# stepper_driver1_a.net
KiCad netlist of a schematic drawn in EAGLE
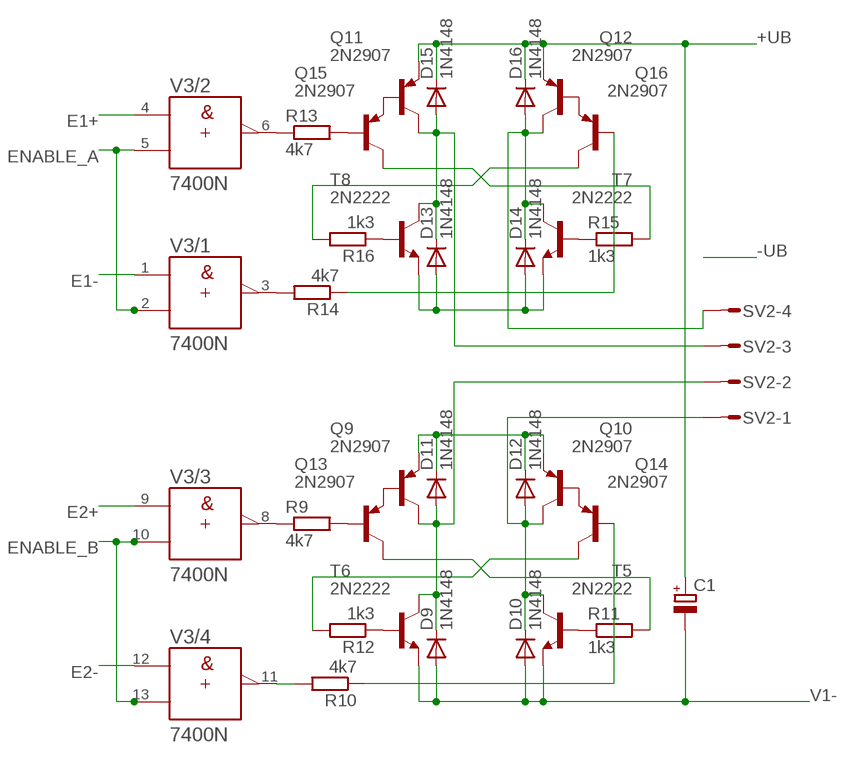
[diagram p0: schematic, sheet 1]

(export (version "E")
  (design (tool "Eeschema 10.0.6"))
  (components
    (comp (ref "C1")
      (value "CPOL-EUE3.5-10")
      (footprint "eagle-import:E3,5-10")
      (libsource (lib "eagle-import") (part "CPOL-EUE3.5-10"))
    )
    (comp (ref "D9")
      (value "1N4148")
      (footprint "eagle-import:D-2.5")
      (libsource (lib "eagle-import") (part "DIODE-D-2.5"))
    )
    (comp (ref "D10")
      (value "1N4148")
      (footprint "eagle-import:D-2.5")
      (libsource (lib "eagle-import") (part "DIODE-D-2.5"))
    )
    (comp (ref "D11")
      (value "1N4148")
      (footprint "eagle-import:D-2.5")
      (libsource (lib "eagle-import") (part "DIODE-D-2.5"))
    )
    (comp (ref "D12")
      (value "1N4148")
      (footprint "eagle-import:D-2.5")
      (libsource (lib "eagle-import") (part "DIODE-D-2.5"))
    )
    (comp (ref "D13")
      (value "1N4148")
      (footprint "eagle-import:D-2.5")
      (libsource (lib "eagle-import") (part "DIODE-D-2.5"))
    )
    (comp (ref "D14")
      (value "1N4148")
      (footprint "eagle-import:D-2.5")
      (libsource (lib "eagle-import") (part "DIODE-D-2.5"))
    )
    (comp (ref "D15")
      (value "1N4148")
      (footprint "eagle-import:D-2.5")
      (libsource (lib "eagle-import") (part "DIODE-D-2.5"))
    )
    (comp (ref "D16")
      (value "1N4148")
      (footprint "eagle-import:D-2.5")
      (libsource (lib "eagle-import") (part "DIODE-D-2.5"))
    )
    (comp (ref "Q9")
      (value "2N2907")
      (footprint "eagle-import:TO18")
      (libsource (lib "eagle-import") (part "2N2907"))
    )
    (comp (ref "Q10")
      (value "2N2907")
      (footprint "eagle-import:TO18")
      (libsource (lib "eagle-import") (part "2N2907"))
    )
    (comp (ref "Q11")
      (value "2N2907")
      (footprint "eagle-import:TO18")
      (libsource (lib "eagle-import") (part "2N2907"))
    )
    (comp (ref "Q12")
      (value "2N2907")
      (footprint "eagle-import:TO18")
      (libsource (lib "eagle-import") (part "2N2907"))
    )
    (comp (ref "Q13")
      (value "2N2907")
      (footprint "eagle-import:TO18")
      (libsource (lib "eagle-import") (part "2N2907"))
    )
    (comp (ref "Q14")
      (value "2N2907")
      (footprint "eagle-import:TO18")
      (libsource (lib "eagle-import") (part "2N2907"))
    )
    (comp (ref "Q15")
      (value "2N2907")
      (footprint "eagle-import:TO18")
      (libsource (lib "eagle-import") (part "2N2907"))
    )
    (comp (ref "Q16")
      (value "2N2907")
      (footprint "eagle-import:TO18")
      (libsource (lib "eagle-import") (part "2N2907"))
    )
    (comp (ref "R9")
      (value "4k7")
      (footprint "eagle-import:0207_10")
      (libsource (lib "eagle-import") (part "R-EU_0207/10"))
    )
    (comp (ref "R10")
      (value "4k7")
      (footprint "eagle-import:0207_12")
      (libsource (lib "eagle-import") (part "R-EU_0207/12"))
    )
    (comp (ref "R11")
      (value "1k3")
      (footprint "eagle-import:0207_10")
      (libsource (lib "eagle-import") (part "R-EU_0207/10"))
    )
    (comp (ref "R12")
      (value "1k3")
      (footprint "eagle-import:0207_10")
      (libsource (lib "eagle-import") (part "R-EU_0207/10"))
    )
    (comp (ref "R13")
      (value "4k7")
      (footprint "eagle-import:0207_10")
      (libsource (lib "eagle-import") (part "R-EU_0207/10"))
    )
    (comp (ref "R14")
      (value "4k7")
      (footprint "eagle-import:0207_10")
      (libsource (lib "eagle-import") (part "R-EU_0207/10"))
    )
    (comp (ref "R15")
      (value "1k3")
      (footprint "eagle-import:0207_10")
      (libsource (lib "eagle-import") (part "R-EU_0207/10"))
    )
    (comp (ref "R16")
      (value "1k3")
      (footprint "eagle-import:0207_10")
      (libsource (lib "eagle-import") (part "R-EU_0207/10"))
    )
    (comp (ref "SV2")
      (value "S04P")
      (footprint "eagle-import:S04P")
      (libsource (lib "eagle-import") (part "S04P"))
    )
    (comp (ref "T5")
      (value "2N2222")
      (footprint "eagle-import:TO18")
      (libsource (lib "eagle-import") (part "2N2222"))
    )
    (comp (ref "T6")
      (value "2N2222")
      (footprint "eagle-import:TO18")
      (libsource (lib "eagle-import") (part "2N2222"))
    )
    (comp (ref "T7")
      (value "2N2222")
      (footprint "eagle-import:TO18")
      (libsource (lib "eagle-import") (part "2N2222"))
    )
    (comp (ref "T8")
      (value "2N2222")
      (footprint "eagle-import:TO18")
      (libsource (lib "eagle-import") (part "2N2222"))
    )
    (comp (ref "V3")
      (value "7400N")
      (footprint "eagle-import:DIL14")
      (libsource (lib "eagle-import") (part "7400N"))
    )
  )
  (nets
    (net (code "1") (name "/+UB") (class "Default")
      (node (ref "C1") (pin "+") (pinfunction "+_+") (pintype "passive"))
      (node (ref "D11") (pin "C") (pinfunction "C_C") (pintype "passive"))
      (node (ref "D12") (pin "C") (pinfunction "C_C") (pintype "passive"))
      (node (ref "D15") (pin "C") (pinfunction "C_C") (pintype "passive"))
      (node (ref "D16") (pin "C") (pinfunction "C_C") (pintype "passive"))
      (node (ref "Q10") (pin "1") (pinfunction "E_1") (pintype "passive"))
      (node (ref "Q11") (pin "1") (pinfunction "E_1") (pintype "passive"))
      (node (ref "Q12") (pin "1") (pinfunction "E_1") (pintype "passive"))
      (node (ref "Q9") (pin "1") (pinfunction "E_1") (pintype "passive"))
    )
    (net (code "3") (name "/E1+") (class "Default")
      (node (ref "V3") (pin "4") (pinfunction "A_4") (pintype "input"))
    )
    (net (code "4") (name "/E1-") (class "Default")
      (node (ref "V3") (pin "1") (pinfunction "A_1") (pintype "input"))
    )
    (net (code "5") (name "/E2+") (class "Default")
      (node (ref "V3") (pin "9") (pinfunction "A_9") (pintype "input"))
    )
    (net (code "6") (name "/E2-") (class "Default")
      (node (ref "V3") (pin "12") (pinfunction "A_12") (pintype "input"))
    )
    (net (code "7") (name "/ENABLE_A") (class "Default")
      (node (ref "V3") (pin "2") (pinfunction "B_2") (pintype "input"))
      (node (ref "V3") (pin "5") (pinfunction "B_5") (pintype "input"))
    )
    (net (code "8") (name "/ENABLE_B") (class "Default")
      (node (ref "V3") (pin "10") (pinfunction "B_10") (pintype "input"))
      (node (ref "V3") (pin "13") (pinfunction "B_13") (pintype "input"))
    )
    (net (code "9") (name "/V1-") (class "Default")
      (node (ref "C1") (pin "-") (pinfunction "-_-") (pintype "passive"))
      (node (ref "D10") (pin "A") (pinfunction "A_A") (pintype "passive"))
      (node (ref "D13") (pin "A") (pinfunction "A_A") (pintype "passive"))
      (node (ref "D14") (pin "A") (pinfunction "A_A") (pintype "passive"))
      (node (ref "D9") (pin "A") (pinfunction "A_A") (pintype "passive"))
      (node (ref "T5") (pin "1") (pinfunction "E_1") (pintype "passive"))
      (node (ref "T6") (pin "1") (pinfunction "E_1") (pintype "passive"))
      (node (ref "T7") (pin "1") (pinfunction "E_1") (pintype "passive"))
      (node (ref "T8") (pin "1") (pinfunction "E_1") (pintype "passive"))
    )
    (net (code "10") (name "Net-(Q9-C)") (class "Default")
      (node (ref "D11") (pin "A") (pinfunction "A_A") (pintype "passive"))
      (node (ref "D9") (pin "C") (pinfunction "C_C") (pintype "passive"))
      (node (ref "Q9") (pin "3") (pinfunction "C_3") (pintype "passive"))
      (node (ref "SV2") (pin "2") (pinfunction "S_2") (pintype "passive"))
      (node (ref "T6") (pin "3") (pinfunction "C_3") (pintype "passive"))
    )
    (net (code "11") (name "Net-(Q10-B)") (class "Default")
      (node (ref "Q10") (pin "2") (pinfunction "B_2") (pintype "passive"))
      (node (ref "Q14") (pin "1") (pinfunction "E_1") (pintype "passive"))
    )
    (net (code "12") (name "Net-(Q10-C)") (class "Default")
      (node (ref "D10") (pin "C") (pinfunction "C_C") (pintype "passive"))
      (node (ref "D12") (pin "A") (pinfunction "A_A") (pintype "passive"))
      (node (ref "Q10") (pin "3") (pinfunction "C_3") (pintype "passive"))
      (node (ref "SV2") (pin "1") (pinfunction "S_1") (pintype "passive"))
      (node (ref "T5") (pin "3") (pinfunction "C_3") (pintype "passive"))
    )
    (net (code "13") (name "Net-(Q11-B)") (class "Default")
      (node (ref "Q11") (pin "2") (pinfunction "B_2") (pintype "passive"))
      (node (ref "Q15") (pin "1") (pinfunction "E_1") (pintype "passive"))
    )
    (net (code "14") (name "Net-(Q11-C)") (class "Default")
      (node (ref "D13") (pin "C") (pinfunction "C_C") (pintype "passive"))
      (node (ref "D15") (pin "A") (pinfunction "A_A") (pintype "passive"))
      (node (ref "Q11") (pin "3") (pinfunction "C_3") (pintype "passive"))
      (node (ref "SV2") (pin "3") (pinfunction "S_3") (pintype "passive"))
      (node (ref "T8") (pin "3") (pinfunction "C_3") (pintype "passive"))
    )
    (net (code "15") (name "Net-(Q12-B)") (class "Default")
      (node (ref "Q12") (pin "2") (pinfunction "B_2") (pintype "passive"))
      (node (ref "Q16") (pin "1") (pinfunction "E_1") (pintype "passive"))
    )
    (net (code "16") (name "Net-(Q12-C)") (class "Default")
      (node (ref "D14") (pin "C") (pinfunction "C_C") (pintype "passive"))
      (node (ref "D16") (pin "A") (pinfunction "A_A") (pintype "passive"))
      (node (ref "Q12") (pin "3") (pinfunction "C_3") (pintype "passive"))
      (node (ref "SV2") (pin "4") (pinfunction "S_4") (pintype "passive"))
      (node (ref "T7") (pin "3") (pinfunction "C_3") (pintype "passive"))
    )
    (net (code "17") (name "Net-(Q13-B)") (class "Default")
      (node (ref "Q13") (pin "2") (pinfunction "B_2") (pintype "passive"))
      (node (ref "R9") (pin "2") (pinfunction "2_2") (pintype "passive"))
    )
    (net (code "18") (name "Net-(Q13-C)") (class "Default")
      (node (ref "Q13") (pin "3") (pinfunction "C_3") (pintype "passive"))
      (node (ref "R11") (pin "2") (pinfunction "2_2") (pintype "passive"))
    )
    (net (code "19") (name "Net-(Q13-E)") (class "Default")
      (node (ref "Q13") (pin "1") (pinfunction "E_1") (pintype "passive"))
      (node (ref "Q9") (pin "2") (pinfunction "B_2") (pintype "passive"))
    )
    (net (code "20") (name "Net-(Q14-B)") (class "Default")
      (node (ref "Q14") (pin "2") (pinfunction "B_2") (pintype "passive"))
      (node (ref "R10") (pin "1") (pinfunction "1_1") (pintype "passive"))
    )
    (net (code "21") (name "Net-(Q14-C)") (class "Default")
      (node (ref "Q14") (pin "3") (pinfunction "C_3") (pintype "passive"))
      (node (ref "R12") (pin "2") (pinfunction "2_2") (pintype "passive"))
    )
    (net (code "22") (name "Net-(Q15-B)") (class "Default")
      (node (ref "Q15") (pin "2") (pinfunction "B_2") (pintype "passive"))
      (node (ref "R13") (pin "2") (pinfunction "2_2") (pintype "passive"))
    )
    (net (code "23") (name "Net-(Q15-C)") (class "Default")
      (node (ref "Q15") (pin "3") (pinfunction "C_3") (pintype "passive"))
      (node (ref "R15") (pin "2") (pinfunction "2_2") (pintype "passive"))
    )
    (net (code "24") (name "Net-(Q16-B)") (class "Default")
      (node (ref "Q16") (pin "2") (pinfunction "B_2") (pintype "passive"))
      (node (ref "R14") (pin "1") (pinfunction "1_1") (pintype "passive"))
    )
    (net (code "25") (name "Net-(Q16-C)") (class "Default")
      (node (ref "Q16") (pin "3") (pinfunction "C_3") (pintype "passive"))
      (node (ref "R16") (pin "2") (pinfunction "2_2") (pintype "passive"))
    )
    (net (code "26") (name "Net-(T5-B)") (class "Default")
      (node (ref "R11") (pin "1") (pinfunction "1_1") (pintype "passive"))
      (node (ref "T5") (pin "2") (pinfunction "B_2") (pintype "passive"))
    )
    (net (code "27") (name "Net-(T6-B)") (class "Default")
      (node (ref "R12") (pin "1") (pinfunction "1_1") (pintype "passive"))
      (node (ref "T6") (pin "2") (pinfunction "B_2") (pintype "passive"))
    )
    (net (code "28") (name "Net-(T7-B)") (class "Default")
      (node (ref "R15") (pin "1") (pinfunction "1_1") (pintype "passive"))
      (node (ref "T7") (pin "2") (pinfunction "B_2") (pintype "passive"))
    )
    (net (code "29") (name "Net-(T8-B)") (class "Default")
      (node (ref "R16") (pin "1") (pinfunction "1_1") (pintype "passive"))
      (node (ref "T8") (pin "2") (pinfunction "B_2") (pintype "passive"))
    )
    (net (code "30") (name "Net-(V3C-Y)") (class "Default")
      (node (ref "R14") (pin "2") (pinfunction "2_2") (pintype "passive"))
      (node (ref "V3") (pin "3") (pinfunction "Y_3") (pintype "output"))
    )
    (net (code "31") (name "Net-(V3D-Y)") (class "Default")
      (node (ref "R13") (pin "1") (pinfunction "1_1") (pintype "passive"))
      (node (ref "V3") (pin "6") (pinfunction "Y_6") (pintype "output"))
    )
    (net (code "32") (name "Net-(V3E-Y)") (class "Default")
      (node (ref "R9") (pin "1") (pinfunction "1_1") (pintype "passive"))
      (node (ref "V3") (pin "8") (pinfunction "Y_8") (pintype "output"))
    )
    (net (code "33") (name "Net-(V3F-Y)") (class "Default")
      (node (ref "R10") (pin "2") (pinfunction "2_2") (pintype "passive"))
      (node (ref "V3") (pin "11") (pinfunction "Y_11") (pintype "output"))
    )
  )
)
